# board.net
KiCad netlist of a schematic drawn in EAGLE
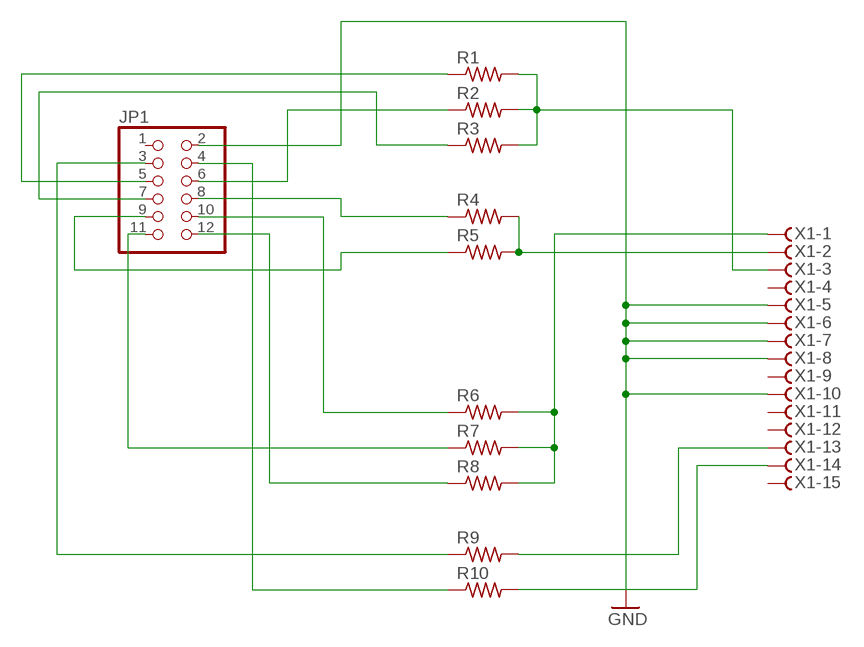
[diagram p0: schematic, sheet 1]

(export (version "E")
  (design (tool "Eeschema 10.0.6"))
  (components
    (comp (ref "JP1")
      (value "PINHD-2X6")
      (footprint "eagle-import:2X06")
      (libsource (lib "eagle-import") (part "PINHD-2X6"))
    )
    (comp (ref "R1")
      (value "R-US_R0805")
      (footprint "eagle-import:R0805")
      (libsource (lib "eagle-import") (part "R-US_R0805"))
    )
    (comp (ref "R2")
      (value "R-US_R0805")
      (footprint "eagle-import:R0805")
      (libsource (lib "eagle-import") (part "R-US_R0805"))
    )
    (comp (ref "R3")
      (value "R-US_R0805")
      (footprint "eagle-import:R0805")
      (libsource (lib "eagle-import") (part "R-US_R0805"))
    )
    (comp (ref "R4")
      (value "R-US_R0805")
      (footprint "eagle-import:R0805")
      (libsource (lib "eagle-import") (part "R-US_R0805"))
    )
    (comp (ref "R5")
      (value "R-US_R0805")
      (footprint "eagle-import:R0805")
      (libsource (lib "eagle-import") (part "R-US_R0805"))
    )
    (comp (ref "R6")
      (value "R-US_R0805")
      (footprint "eagle-import:R0805")
      (libsource (lib "eagle-import") (part "R-US_R0805"))
    )
    (comp (ref "R7")
      (value "R-US_R0805")
      (footprint "eagle-import:R0805")
      (libsource (lib "eagle-import") (part "R-US_R0805"))
    )
    (comp (ref "R8")
      (value "R-US_R0805")
      (footprint "eagle-import:R0805")
      (libsource (lib "eagle-import") (part "R-US_R0805"))
    )
    (comp (ref "R9")
      (value "R-US_R0805")
      (footprint "eagle-import:R0805")
      (libsource (lib "eagle-import") (part "R-US_R0805"))
    )
    (comp (ref "R10")
      (value "R-US_R0805")
      (footprint "eagle-import:R0805")
      (libsource (lib "eagle-import") (part "R-US_R0805"))
    )
    (comp (ref "X1")
      (value "F15HDHS")
      (footprint "eagle-import:HDF15H")
      (libsource (lib "eagle-import") (part "F15?SHDH"))
    )
  )
  (nets
    (net (code "1") (name "GND") (class "Default")
      (node (ref "JP1") (pin "2") (pinfunction "2_2") (pintype "passive"))
      (node (ref "X1") (pin "10") (pinfunction "F_10") (pintype "passive"))
      (node (ref "X1") (pin "5") (pinfunction "F_5") (pintype "passive"))
      (node (ref "X1") (pin "6") (pinfunction "F_6") (pintype "passive"))
      (node (ref "X1") (pin "7") (pinfunction "F_7") (pintype "passive"))
      (node (ref "X1") (pin "8") (pinfunction "F_8") (pintype "passive"))
    )
    (net (code "2") (name "Net-(JP1-Pad3)") (class "Default")
      (node (ref "JP1") (pin "3") (pinfunction "3_3") (pintype "passive"))
      (node (ref "R9") (pin "1") (pinfunction "1_1") (pintype "passive"))
    )
    (net (code "3") (name "Net-(JP1-Pad4)") (class "Default")
      (node (ref "JP1") (pin "4") (pinfunction "4_4") (pintype "passive"))
      (node (ref "R10") (pin "1") (pinfunction "1_1") (pintype "passive"))
    )
    (net (code "4") (name "Net-(JP1-Pad5)") (class "Default")
      (node (ref "JP1") (pin "5") (pinfunction "5_5") (pintype "passive"))
      (node (ref "R1") (pin "1") (pinfunction "1_1") (pintype "passive"))
    )
    (net (code "5") (name "Net-(JP1-Pad6)") (class "Default")
      (node (ref "JP1") (pin "6") (pinfunction "6_6") (pintype "passive"))
      (node (ref "R2") (pin "1") (pinfunction "1_1") (pintype "passive"))
    )
    (net (code "6") (name "Net-(JP1-Pad7)") (class "Default")
      (node (ref "JP1") (pin "7") (pinfunction "7_7") (pintype "passive"))
      (node (ref "R3") (pin "1") (pinfunction "1_1") (pintype "passive"))
    )
    (net (code "7") (name "Net-(JP1-Pad8)") (class "Default")
      (node (ref "JP1") (pin "8") (pinfunction "8_8") (pintype "passive"))
      (node (ref "R4") (pin "1") (pinfunction "1_1") (pintype "passive"))
    )
    (net (code "8") (name "Net-(JP1-Pad9)") (class "Default")
      (node (ref "JP1") (pin "9") (pinfunction "9_9") (pintype "passive"))
      (node (ref "R5") (pin "1") (pinfunction "1_1") (pintype "passive"))
    )
    (net (code "9") (name "Net-(JP1-Pad10)") (class "Default")
      (node (ref "JP1") (pin "10") (pinfunction "10_10") (pintype "passive"))
      (node (ref "R6") (pin "1") (pinfunction "1_1") (pintype "passive"))
    )
    (net (code "10") (name "Net-(JP1-Pad11)") (class "Default")
      (node (ref "JP1") (pin "11") (pinfunction "11_11") (pintype "passive"))
      (node (ref "R7") (pin "1") (pinfunction "1_1") (pintype "passive"))
    )
    (net (code "11") (name "Net-(JP1-Pad12)") (class "Default")
      (node (ref "JP1") (pin "12") (pinfunction "12_12") (pintype "passive"))
      (node (ref "R8") (pin "1") (pinfunction "1_1") (pintype "passive"))
    )
    (net (code "12") (name "Net-(X1A-F)") (class "Default")
      (node (ref "R6") (pin "2") (pinfunction "2_2") (pintype "passive"))
      (node (ref "R7") (pin "2") (pinfunction "2_2") (pintype "passive"))
      (node (ref "R8") (pin "2") (pinfunction "2_2") (pintype "passive"))
      (node (ref "X1") (pin "1") (pinfunction "F_1") (pintype "passive"))
    )
    (net (code "13") (name "Net-(X1E-F)") (class "Default")
      (node (ref "R9") (pin "2") (pinfunction "2_2") (pintype "passive"))
      (node (ref "X1") (pin "13") (pinfunction "F_13") (pintype "passive"))
    )
    (net (code "14") (name "Net-(X1F-F)") (class "Default")
      (node (ref "R10") (pin "2") (pinfunction "2_2") (pintype "passive"))
      (node (ref "X1") (pin "14") (pinfunction "F_14") (pintype "passive"))
    )
    (net (code "15") (name "Net-(X1H-F)") (class "Default")
      (node (ref "R4") (pin "2") (pinfunction "2_2") (pintype "passive"))
      (node (ref "R5") (pin "2") (pinfunction "2_2") (pintype "passive"))
      (node (ref "X1") (pin "2") (pinfunction "F_2") (pintype "passive"))
    )
    (net (code "16") (name "Net-(X1I-F)") (class "Default")
      (node (ref "R1") (pin "2") (pinfunction "2_2") (pintype "passive"))
      (node (ref "R2") (pin "2") (pinfunction "2_2") (pintype "passive"))
      (node (ref "R3") (pin "2") (pinfunction "2_2") (pintype "passive"))
      (node (ref "X1") (pin "3") (pinfunction "F_3") (pintype "passive"))
    )
    (net (code "17") (name "unconnected-(JP1-Pad1)") (class "Default")
      (node (ref "JP1") (pin "1") (pinfunction "1_1") (pintype "passive"))
    )
    (net (code "18") (name "unconnected-(X1C-F-Pad11)") (class "Default")
      (node (ref "X1") (pin "11") (pinfunction "F_11") (pintype "passive"))
    )
    (net (code "19") (name "unconnected-(X1D-F-Pad12)") (class "Default")
      (node (ref "X1") (pin "12") (pinfunction "F_12") (pintype "passive"))
    )
    (net (code "20") (name "unconnected-(X1G-F-Pad15)") (class "Default")
      (node (ref "X1") (pin "15") (pinfunction "F_15") (pintype "passive"))
    )
    (net (code "21") (name "unconnected-(X1J-F-Pad4)") (class "Default")
      (node (ref "X1") (pin "4") (pinfunction "F_4") (pintype "passive"))
    )
    (net (code "22") (name "unconnected-(X1O-F-Pad9)") (class "Default")
      (node (ref "X1") (pin "9") (pinfunction "F_9") (pintype "passive"))
    )
  )
)
